# Power.net
KiCad netlist of a schematic drawn in Altium Designer
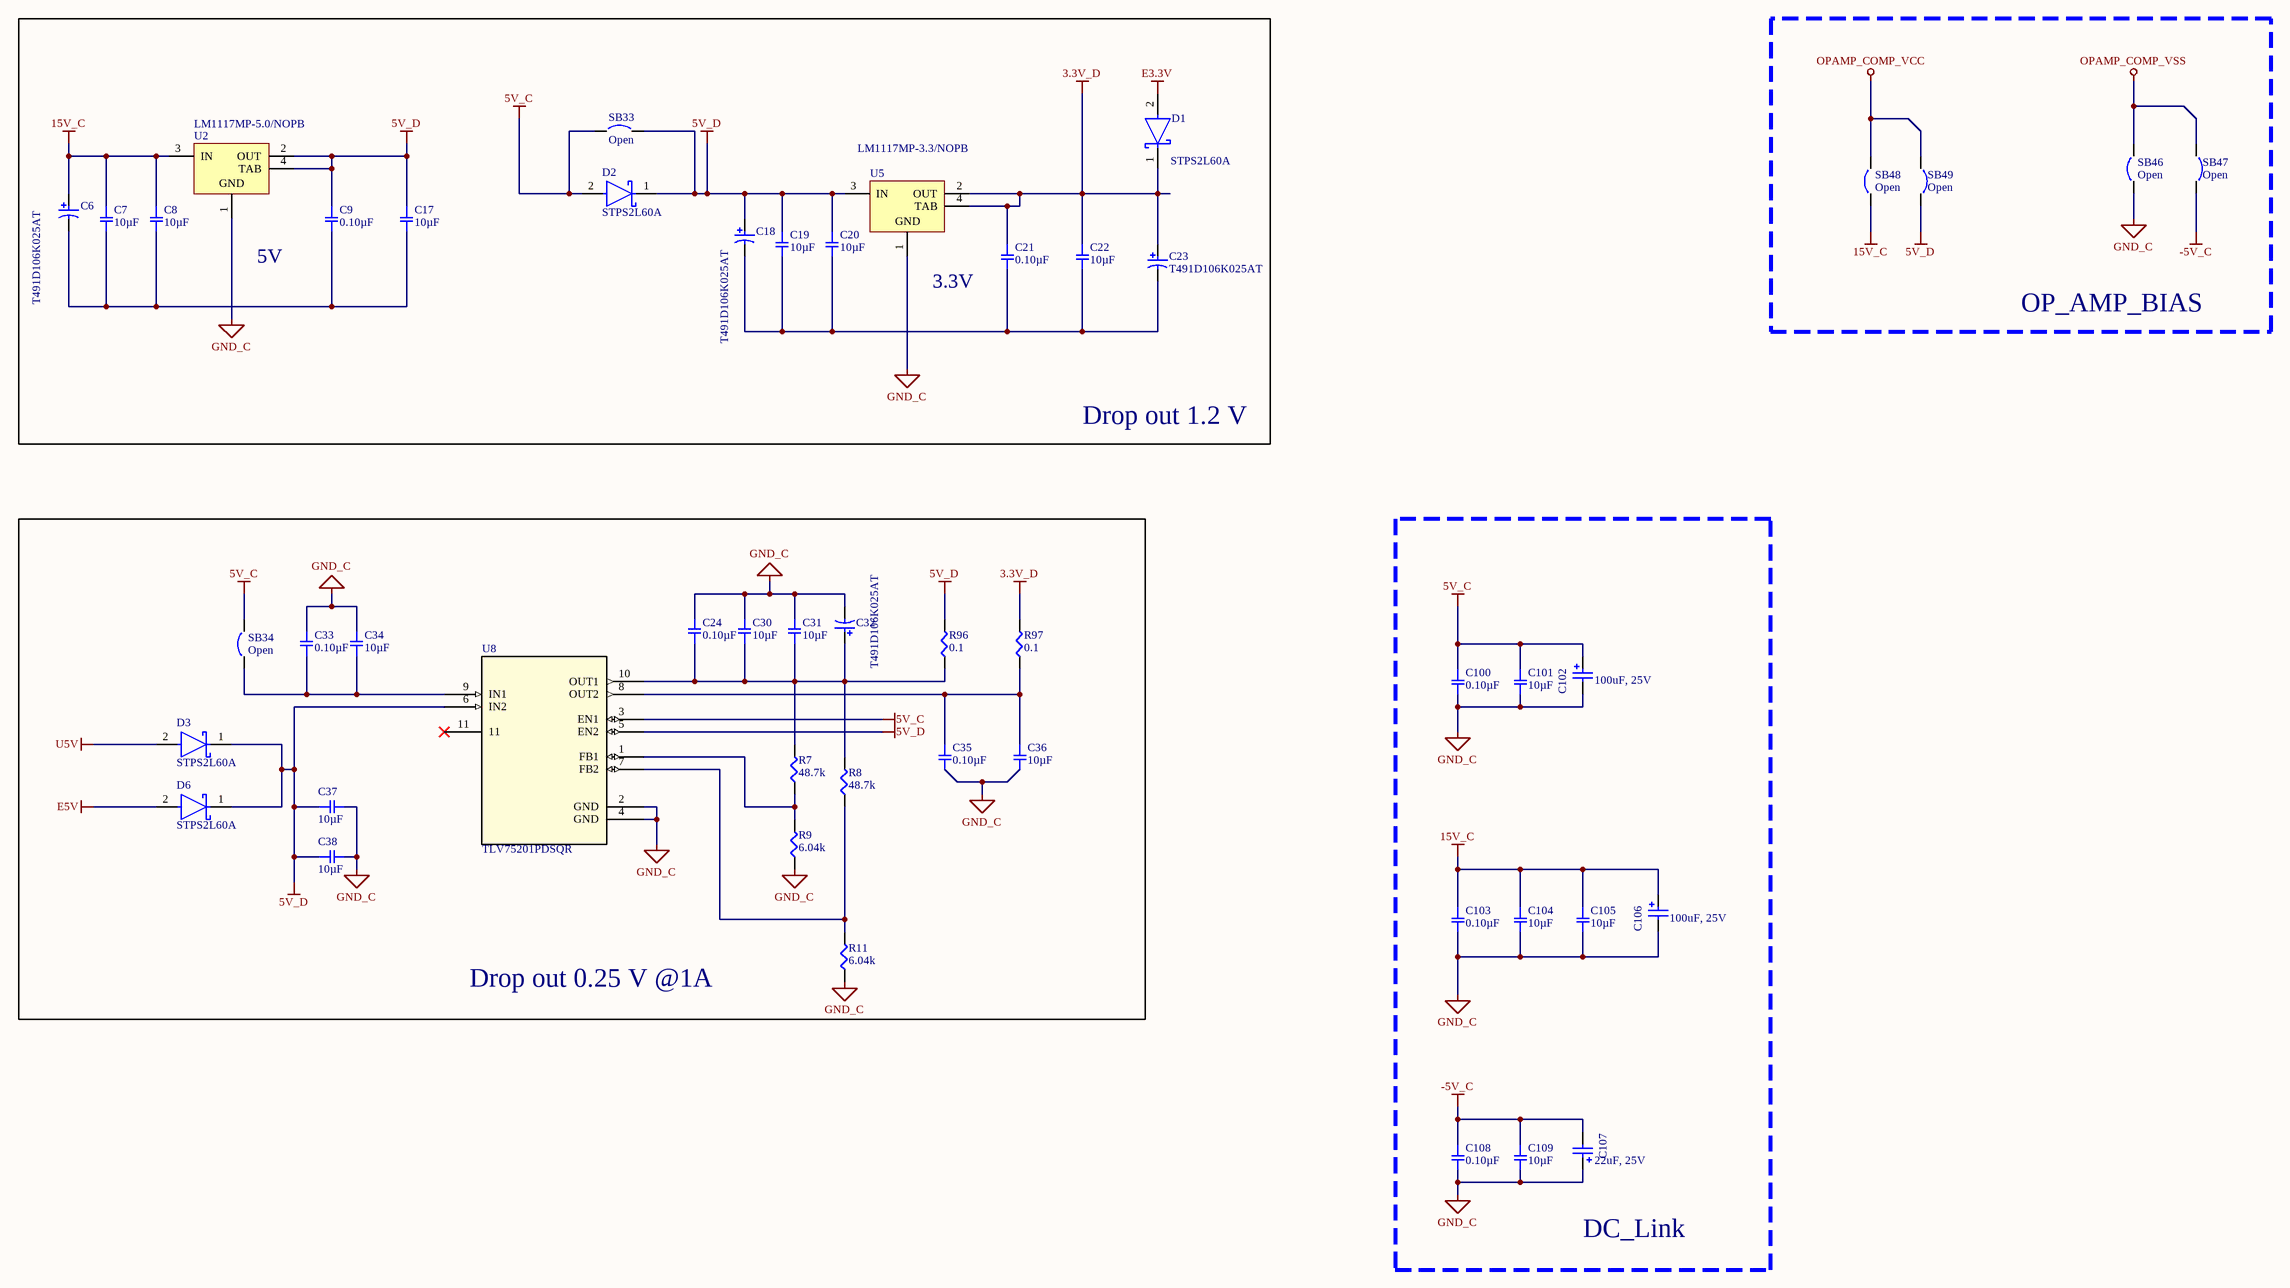
[diagram p0: Power.SchDoc]

(export (version "E")
  (design (tool "Eeschema 10.0.6"))
  (components
    (comp (ref "C6")
      (value "T491D106K025AT")
      (footprint "KEMT-T491-D_L")
      (description "Tantalum Capacitor, 10 uF, +/- 10%, 25 V, -55 to 125 degC, 2-Pin SMD, RoHS, Tape and Reel")
      (fields (field (name "MANUFACTURER") "Kemet") (field (name "VOLTAGE") "25VDC"))
      (libsource (lib "Altium Content Vault") (part "CAP-P-2"))
    )
    (comp (ref "C7")
      (value "10µF")
      (footprint "SMD-0805C")
      (description "CAP CER 10UF 10V X7R 0805")
      (fields
        (field (name "DIGI-KEY PART NUMBER") "490-10674-1-ND")
        (field (name "PART NUMBER") "GCM21BR71A106KE22L")
      )
      (libsource (lib "capacitor_murata_0805") (part "GCM21BR71A106KE22L"))
    )
    (comp (ref "C8")
      (value "10µF")
      (footprint "SMD-0805C")
      (description "CAP CER 10UF 10V X7R 0805")
      (fields
        (field (name "DIGI-KEY PART NUMBER") "490-10674-1-ND")
        (field (name "PART NUMBER") "GCM21BR71A106KE22L")
      )
      (libsource (lib "capacitor_murata_0805") (part "GCM21BR71A106KE22L"))
    )
    (comp (ref "C9")
      (value "0.10µF")
      (footprint "SMD-0805C")
      (description "CAP CER 0.1UF 100V X7R 0805")
      (fields
        (field (name "DIGI-KEY PART NUMBER") "490-5825-1-ND")
        (field (name "PART NUMBER") "GCJ21BR72A104KA01L")
      )
      (libsource (lib "capacitor_murata_0805") (part "GCJ21BR72A104KA01L"))
    )
    (comp (ref "C17")
      (value "10µF")
      (footprint "SMD-0805C")
      (description "CAP CER 10UF 10V X7R 0805")
      (fields
        (field (name "DIGI-KEY PART NUMBER") "490-10674-1-ND")
        (field (name "PART NUMBER") "GCM21BR71A106KE22L")
      )
      (libsource (lib "capacitor_murata_0805") (part "GCM21BR71A106KE22L"))
    )
    (comp (ref "C18")
      (value "T491D106K025AT")
      (footprint "KEMT-T491-D_L")
      (description "Tantalum Capacitor, 10 uF, +/- 10%, 25 V, -55 to 125 degC, 2-Pin SMD, RoHS, Tape and Reel")
      (fields (field (name "MANUFACTURER") "Kemet") (field (name "VOLTAGE") "25VDC"))
      (libsource (lib "Altium Content Vault") (part "CAP-P-2"))
    )
    (comp (ref "C19")
      (value "10µF")
      (footprint "SMD-0805C")
      (description "CAP CER 10UF 10V X7R 0805")
      (fields
        (field (name "DIGI-KEY PART NUMBER") "490-10674-1-ND")
        (field (name "PART NUMBER") "GCM21BR71A106KE22L")
      )
      (libsource (lib "capacitor_murata_0805") (part "GCM21BR71A106KE22L"))
    )
    (comp (ref "C20")
      (value "10µF")
      (footprint "SMD-0805C")
      (description "CAP CER 10UF 10V X7R 0805")
      (fields
        (field (name "DIGI-KEY PART NUMBER") "490-10674-1-ND")
        (field (name "PART NUMBER") "GCM21BR71A106KE22L")
      )
      (libsource (lib "capacitor_murata_0805") (part "GCM21BR71A106KE22L"))
    )
    (comp (ref "C21")
      (value "0.10µF")
      (footprint "SMD-0805C")
      (description "CAP CER 0.1UF 100V X7R 0805")
      (fields
        (field (name "DIGI-KEY PART NUMBER") "490-5825-1-ND")
        (field (name "PART NUMBER") "GCJ21BR72A104KA01L")
      )
      (libsource (lib "capacitor_murata_0805") (part "GCJ21BR72A104KA01L"))
    )
    (comp (ref "C22")
      (value "10µF")
      (footprint "SMD-0805C")
      (description "CAP CER 10UF 10V X7R 0805")
      (fields
        (field (name "DIGI-KEY PART NUMBER") "490-10674-1-ND")
        (field (name "PART NUMBER") "GCM21BR71A106KE22L")
      )
      (libsource (lib "capacitor_murata_0805") (part "GCM21BR71A106KE22L"))
    )
    (comp (ref "C23")
      (value "T491D106K025AT")
      (footprint "KEMT-T491-D_L")
      (description "Tantalum Capacitor, 10 uF, +/- 10%, 25 V, -55 to 125 degC, 2-Pin SMD, RoHS, Tape and Reel")
      (fields (field (name "MANUFACTURER") "Kemet") (field (name "VOLTAGE") "25VDC"))
      (libsource (lib "Altium Content Vault") (part "CAP-P-2"))
    )
    (comp (ref "C24")
      (value "0.10µF")
      (footprint "SMD-0805C")
      (description "CAP CER 0.1UF 100V X7R 0805")
      (fields
        (field (name "DIGI-KEY PART NUMBER") "490-5825-1-ND")
        (field (name "PART NUMBER") "GCJ21BR72A104KA01L")
      )
      (libsource (lib "capacitor_murata_0805") (part "GCJ21BR72A104KA01L"))
    )
    (comp (ref "C30")
      (value "10µF")
      (footprint "SMD-0805C")
      (description "CAP CER 10UF 10V X7R 0805")
      (fields
        (field (name "DIGI-KEY PART NUMBER") "490-10674-1-ND")
        (field (name "PART NUMBER") "GCM21BR71A106KE22L")
      )
      (libsource (lib "capacitor_murata_0805") (part "GCM21BR71A106KE22L"))
    )
    (comp (ref "C31")
      (value "10µF")
      (footprint "SMD-0805C")
      (description "CAP CER 10UF 10V X7R 0805")
      (fields
        (field (name "DIGI-KEY PART NUMBER") "490-10674-1-ND")
        (field (name "PART NUMBER") "GCM21BR71A106KE22L")
      )
      (libsource (lib "capacitor_murata_0805") (part "GCM21BR71A106KE22L"))
    )
    (comp (ref "C32")
      (value "T491D106K025AT")
      (footprint "KEMT-T491-D_L")
      (description "Tantalum Capacitor, 10 uF, +/- 10%, 25 V, -55 to 125 degC, 2-Pin SMD, RoHS, Tape and Reel")
      (fields (field (name "MANUFACTURER") "Kemet") (field (name "VOLTAGE") "25VDC"))
      (libsource (lib "Altium Content Vault") (part "CAP-P-2"))
    )
    (comp (ref "C33")
      (value "0.10µF")
      (footprint "SMD-0805C")
      (description "CAP CER 0.1UF 100V X7R 0805")
      (fields
        (field (name "DIGI-KEY PART NUMBER") "490-5825-1-ND")
        (field (name "PART NUMBER") "GCJ21BR72A104KA01L")
      )
      (libsource (lib "capacitor_murata_0805") (part "GCJ21BR72A104KA01L"))
    )
    (comp (ref "C34")
      (value "10µF")
      (footprint "SMD-0805C")
      (description "CAP CER 10UF 10V X7R 0805")
      (fields
        (field (name "DIGI-KEY PART NUMBER") "490-10674-1-ND")
        (field (name "PART NUMBER") "GCM21BR71A106KE22L")
      )
      (libsource (lib "capacitor_murata_0805") (part "GCM21BR71A106KE22L"))
    )
    (comp (ref "C35")
      (value "0.10µF")
      (footprint "SMD-0805C")
      (description "CAP CER 0.1UF 100V X7R 0805")
      (fields
        (field (name "DIGI-KEY PART NUMBER") "490-5825-1-ND")
        (field (name "PART NUMBER") "GCJ21BR72A104KA01L")
      )
      (libsource (lib "capacitor_murata_0805") (part "GCJ21BR72A104KA01L"))
    )
    (comp (ref "C36")
      (value "10µF")
      (footprint "SMD-0805C")
      (description "CAP CER 10UF 10V X7R 0805")
      (fields
        (field (name "DIGI-KEY PART NUMBER") "490-10674-1-ND")
        (field (name "PART NUMBER") "GCM21BR71A106KE22L")
      )
      (libsource (lib "capacitor_murata_0805") (part "GCM21BR71A106KE22L"))
    )
    (comp (ref "C37")
      (value "10µF")
      (footprint "SMD-0805C")
      (description "CAP CER 10UF 10V X7R 0805")
      (fields
        (field (name "DIGI-KEY PART NUMBER") "490-10674-1-ND")
        (field (name "PART NUMBER") "GCM21BR71A106KE22L")
      )
      (libsource (lib "capacitor_murata_0805") (part "GCM21BR71A106KE22L"))
    )
    (comp (ref "C38")
      (value "10µF")
      (footprint "SMD-0805C")
      (description "CAP CER 10UF 10V X7R 0805")
      (fields
        (field (name "DIGI-KEY PART NUMBER") "490-10674-1-ND")
        (field (name "PART NUMBER") "GCM21BR71A106KE22L")
      )
      (libsource (lib "capacitor_murata_0805") (part "GCM21BR71A106KE22L"))
    )
    (comp (ref "C100")
      (value "0.10µF")
      (footprint "SMD-0805C")
      (description "CAP CER 0.1UF 100V X7R 0805")
      (fields
        (field (name "DIGI-KEY PART NUMBER") "490-5825-1-ND")
        (field (name "PART NUMBER") "GCJ21BR72A104KA01L")
      )
      (libsource (lib "capacitor_murata_0805") (part "GCJ21BR72A104KA01L"))
    )
    (comp (ref "C101")
      (value "10µF")
      (footprint "SMD-0805C")
      (description "CAP CER 10UF 10V X7R 0805")
      (fields
        (field (name "DIGI-KEY PART NUMBER") "490-10674-1-ND")
        (field (name "PART NUMBER") "GCM21BR71A106KE22L")
      )
      (libsource (lib "capacitor_murata_0805") (part "GCM21BR71A106KE22L"))
    )
    (comp (ref "C102")
      (value "100uF, 25V")
      (footprint "WCAP-ASLU_6.3x7.7")
      (description "WCAP-ASLU Aluminium Electrolytic Capacitors, D6.3mm x L7.7mm, 100uF, +/-20%, 25VDC")
      (fields (field (name "PART NUMBER") "865090445008") (field (name "PUBLISHER") "Wurth Elektronik"))
      (libsource (lib "Altium_WCAP-ASLU_SMD") (part "865090445008"))
    )
    (comp (ref "C103")
      (value "0.10µF")
      (footprint "SMD-0805C")
      (description "CAP CER 0.1UF 100V X7R 0805")
      (fields
        (field (name "DIGI-KEY PART NUMBER") "490-5825-1-ND")
        (field (name "PART NUMBER") "GCJ21BR72A104KA01L")
      )
      (libsource (lib "capacitor_murata_0805") (part "GCJ21BR72A104KA01L"))
    )
    (comp (ref "C104")
      (value "10µF")
      (footprint "SMD-0805C")
      (description "CAP CER 10UF 10V X7R 0805")
      (fields
        (field (name "DIGI-KEY PART NUMBER") "490-10674-1-ND")
        (field (name "PART NUMBER") "GCM21BR71A106KE22L")
      )
      (libsource (lib "capacitor_murata_0805") (part "GCM21BR71A106KE22L"))
    )
    (comp (ref "C105")
      (value "10µF")
      (footprint "SMD-0805C")
      (description "CAP CER 10UF 10V X7R 0805")
      (fields
        (field (name "DIGI-KEY PART NUMBER") "490-10674-1-ND")
        (field (name "PART NUMBER") "GCM21BR71A106KE22L")
      )
      (libsource (lib "capacitor_murata_0805") (part "GCM21BR71A106KE22L"))
    )
    (comp (ref "C106")
      (value "100uF, 25V")
      (footprint "WCAP-ASLU_6.3x7.7")
      (description "WCAP-ASLU Aluminium Electrolytic Capacitors, D6.3mm x L7.7mm, 100uF, +/-20%, 25VDC")
      (fields (field (name "PART NUMBER") "865090445008") (field (name "PUBLISHER") "Wurth Elektronik"))
      (libsource (lib "Altium_WCAP-ASLU_SMD") (part "865090445008"))
    )
    (comp (ref "C107")
      (value "22uF, 25V")
      (footprint "WCAP-ASLU_5x5.5")
      (description "WCAP-ASLU Aluminium Electrolytic Capacitors, D5mm x L5.5mm, 22uF, +/-20%, 25VDC")
      (fields (field (name "PART NUMBER") "865090442004") (field (name "PUBLISHER") "Wurth Elektronik"))
      (libsource (lib "Altium_WCAP-ASLU_SMD") (part "865090442004"))
    )
    (comp (ref "C108")
      (value "0.10µF")
      (footprint "SMD-0805C")
      (description "CAP CER 0.1UF 100V X7R 0805")
      (fields
        (field (name "DIGI-KEY PART NUMBER") "490-5825-1-ND")
        (field (name "PART NUMBER") "GCJ21BR72A104KA01L")
      )
      (libsource (lib "capacitor_murata_0805") (part "GCJ21BR72A104KA01L"))
    )
    (comp (ref "C109")
      (value "10µF")
      (footprint "SMD-0805C")
      (description "CAP CER 10UF 10V X7R 0805")
      (fields
        (field (name "DIGI-KEY PART NUMBER") "490-10674-1-ND")
        (field (name "PART NUMBER") "GCM21BR71A106KE22L")
      )
      (libsource (lib "capacitor_murata_0805") (part "GCM21BR71A106KE22L"))
    )
    (comp (ref "D1")
      (value "STPS2L60A")
      (footprint "FP-SMA-MFG")
      (description "DIODE SCHOTTKY 60V 2A SMA")
      (fields
        (field (name "OCTOPART") "https://octopart.com/stps2l60a-stmicroelectronics-324283")
        (field (name "MANUFACTURER") "STMicroelectronics")
      )
      (libsource (lib "Altium Content Vault") (part "fefb30dabb5d097ae2f038500735429"))
    )
    (comp (ref "D2")
      (value "STPS2L60A")
      (footprint "FP-SMA-MFG")
      (description "DIODE SCHOTTKY 60V 2A SMA")
      (fields
        (field (name "OCTOPART") "https://octopart.com/stps2l60a-stmicroelectronics-324283")
        (field (name "MANUFACTURER") "STMicroelectronics")
      )
      (libsource (lib "Altium Content Vault") (part "fefb30dabb5d097ae2f038500735429"))
    )
    (comp (ref "D3")
      (value "STPS2L60A")
      (footprint "FP-SMA-MFG")
      (description "DIODE SCHOTTKY 60V 2A SMA")
      (fields
        (field (name "OCTOPART") "https://octopart.com/stps2l60a-stmicroelectronics-324283")
        (field (name "MANUFACTURER") "STMicroelectronics")
      )
      (libsource (lib "Altium Content Vault") (part "fefb30dabb5d097ae2f038500735429"))
    )
    (comp (ref "D6")
      (value "STPS2L60A")
      (footprint "FP-SMA-MFG")
      (description "DIODE SCHOTTKY 60V 2A SMA")
      (fields
        (field (name "OCTOPART") "https://octopart.com/stps2l60a-stmicroelectronics-324283")
        (field (name "MANUFACTURER") "STMicroelectronics")
      )
      (libsource (lib "Altium Content Vault") (part "fefb30dabb5d097ae2f038500735429"))
    )
    (comp (ref "R7")
      (value "48.7k")
      (footprint "SMD-0603-RES")
      (description "RES SMD 48.7K OHM 1% 1/10W 0603")
      (fields
        (field (name "PART NUMBER") "ERJ-3EKF4872V")
        (field (name "DIGI-KEY PART NUMBER") "P48.7KHCT-ND")
      )
      (libsource (lib "Panasonic_ERJ_0603") (part "ERJ-3EKF4872V"))
    )
    (comp (ref "R8")
      (value "48.7k")
      (footprint "SMD-0603-RES")
      (description "RES SMD 48.7K OHM 1% 1/10W 0603")
      (fields
        (field (name "PART NUMBER") "ERJ-3EKF4872V")
        (field (name "DIGI-KEY PART NUMBER") "P48.7KHCT-ND")
      )
      (libsource (lib "Panasonic_ERJ_0603") (part "ERJ-3EKF4872V"))
    )
    (comp (ref "R9")
      (value "6.04k")
      (footprint "SMD-0603-RES")
      (description "RES SMD 6.04K OHM 1% 1/10W 0603")
      (fields
        (field (name "PART NUMBER") "ERJ-3EKF6041V")
        (field (name "DIGI-KEY PART NUMBER") "P6.04KHCT-ND")
      )
      (libsource (lib "Panasonic_ERJ_0603") (part "ERJ-3EKF6041V"))
    )
    (comp (ref "R11")
      (value "6.04k")
      (footprint "SMD-0603-RES")
      (description "RES SMD 6.04K OHM 1% 1/10W 0603")
      (fields
        (field (name "PART NUMBER") "ERJ-3EKF6041V")
        (field (name "DIGI-KEY PART NUMBER") "P6.04KHCT-ND")
      )
      (libsource (lib "Panasonic_ERJ_0603") (part "ERJ-3EKF6041V"))
    )
    (comp (ref "R96")
      (value "0.1")
      (footprint "SMD-1206-RES")
      (description "RES SMD 0.1 OHM 1% 1/2W 1206")
      (fields (field (name "PART NUMBER") "ERJ-8BSFR10V") (field (name "DIGI-KEY PART NUMBER") "P17678CT-ND"))
      (libsource (lib "Panasonic_ERJ_1206") (part "ERJ-8BSFR10V"))
    )
    (comp (ref "R97")
      (value "0.1")
      (footprint "SMD-1206-RES")
      (description "RES SMD 0.1 OHM 1% 1/2W 1206")
      (fields (field (name "PART NUMBER") "ERJ-8BSFR10V") (field (name "DIGI-KEY PART NUMBER") "P17678CT-ND"))
      (libsource (lib "Panasonic_ERJ_1206") (part "ERJ-8BSFR10V"))
    )
    (comp (ref "SB33")
      (value "Open")
      (footprint "SB_0603")
      (description "Circuit Breaker")
      (fields (field (name "PUBLISHER") "Altium Limited"))
      (libsource (lib "Edge_Card_Ucc28951") (part "Solder Bridge"))
    )
    (comp (ref "SB34")
      (value "Open")
      (footprint "SB_0603")
      (description "Circuit Breaker")
      (fields (field (name "PUBLISHER") "Altium Limited"))
      (libsource (lib "Edge_Card_Ucc28951") (part "Solder Bridge"))
    )
    (comp (ref "SB46")
      (value "Open")
      (footprint "Solder Bridge - HP")
      (description "Circuit Breaker")
      (fields (field (name "PUBLISHER") "Altium Limited"))
      (libsource (lib "Edge_Card_Ucc28951") (part "Solder Bridge"))
    )
    (comp (ref "SB47")
      (value "Open")
      (footprint "Solder Bridge - HP")
      (description "Circuit Breaker")
      (fields (field (name "PUBLISHER") "Altium Limited"))
      (libsource (lib "") (part "Solder Bridge_1"))
    )
    (comp (ref "SB48")
      (value "Open")
      (footprint "Solder Bridge - HP")
      (description "Circuit Breaker")
      (fields (field (name "PUBLISHER") "Altium Limited"))
      (libsource (lib "Edge_Card_Ucc28951") (part "Solder Bridge"))
    )
    (comp (ref "SB49")
      (value "Open")
      (footprint "Solder Bridge - HP")
      (description "Circuit Breaker")
      (fields (field (name "PUBLISHER") "Altium Limited"))
      (libsource (lib "") (part "Solder Bridge_1"))
    )
    (comp (ref "U2")
      (value "LM1117MP-5.0/NOPB")
      (footprint "DCY0004A_N")
      (description "800mA Low-Dropout Linear Regulator, 4-pin SOT-223, Pb-Free")
      (fields (field (name "MANUFACTURER") "Texas Instruments"))
      (libsource (lib "Altium Content Vault") (part "PM-REG-LM1086-SOT4"))
    )
    (comp (ref "U5")
      (value "LM1117MP-3.3/NOPB")
      (footprint "DCY0004A_L")
      (description "800mA Low-Dropout Linear Regulator, 4-pin SOT-223, Pb-Free")
      (fields (field (name "MANUFACTURER") "Texas Instruments"))
      (libsource (lib "Altium Content Vault") (part "PM-REG-LM1086-SOT4"))
    )
    (comp (ref "U8")
      (value "TLV75201PDSQR")
      (footprint "SON40P200X80_HS-11N")
      (description "No Description Available")
      (fields (field (name "COPYRIGHT") "Copyright (C) 2018 Accelerated Designs. All rights reserved"))
      (libsource (lib "Edge_Card_Ucc28951") (part "TLV75201PDSQR"))
    )
  )
  (nets
    (net (code "1") (name "-5V_C") (class "Default")
      (node (ref "C107") (pin "1") (pinfunction "N_1") (pintype "passive"))
      (node (ref "C108") (pin "1") (pinfunction "1_1") (pintype "passive"))
      (node (ref "C109") (pin "1") (pinfunction "1_1") (pintype "passive"))
      (node (ref "SB47") (pin "1") (pinfunction "1_1") (pintype "passive"))
    )
    (net (code "2") (name "3.3V_D") (class "Default")
      (node (ref "C21") (pin "1") (pinfunction "1_1") (pintype "passive"))
      (node (ref "C22") (pin "1") (pinfunction "1_1") (pintype "passive"))
      (node (ref "C23") (pin "1") (pinfunction "1_1") (pintype "passive"))
      (node (ref "D1") (pin "1") (pinfunction "K_1") (pintype "passive"))
      (node (ref "R97") (pin "2") (pinfunction "2_2") (pintype "passive"))
      (node (ref "U5") (pin "2") (pinfunction "OUT_2") (pintype "power_in"))
      (node (ref "U5") (pin "4") (pinfunction "TAB_4") (pintype "power_in"))
    )
    (net (code "3") (name "5V_C") (class "Default")
      (node (ref "C100") (pin "1") (pinfunction "1_1") (pintype "passive"))
      (node (ref "C101") (pin "1") (pinfunction "1_1") (pintype "passive"))
      (node (ref "C102") (pin "2") (pinfunction "P_2") (pintype "passive"))
      (node (ref "D2") (pin "2") (pinfunction "A_2") (pintype "passive"))
      (node (ref "SB33") (pin "1") (pinfunction "1_1") (pintype "passive"))
      (node (ref "SB34") (pin "2") (pinfunction "2_2") (pintype "passive"))
      (node (ref "U8") (pin "3") (pinfunction "EN1_3") (pintype "bidirectional"))
    )
    (net (code "4") (name "5V_D") (class "Default")
      (node (ref "C17") (pin "1") (pinfunction "1_1") (pintype "passive"))
      (node (ref "C18") (pin "1") (pinfunction "1_1") (pintype "passive"))
      (node (ref "C19") (pin "1") (pinfunction "1_1") (pintype "passive"))
      (node (ref "C20") (pin "1") (pinfunction "1_1") (pintype "passive"))
      (node (ref "C37") (pin "1") (pinfunction "1_1") (pintype "passive"))
      (node (ref "C38") (pin "1") (pinfunction "1_1") (pintype "passive"))
      (node (ref "C9") (pin "1") (pinfunction "1_1") (pintype "passive"))
      (node (ref "D2") (pin "1") (pinfunction "K_1") (pintype "passive"))
      (node (ref "D3") (pin "1") (pinfunction "K_1") (pintype "passive"))
      (node (ref "D6") (pin "1") (pinfunction "K_1") (pintype "passive"))
      (node (ref "R96") (pin "2") (pinfunction "2_2") (pintype "passive"))
      (node (ref "SB33") (pin "2") (pinfunction "2_2") (pintype "passive"))
      (node (ref "SB49") (pin "1") (pinfunction "1_1") (pintype "passive"))
      (node (ref "U2") (pin "2") (pinfunction "OUT_2") (pintype "power_in"))
      (node (ref "U2") (pin "4") (pinfunction "TAB_4") (pintype "power_in"))
      (node (ref "U5") (pin "3") (pinfunction "IN_3") (pintype "power_in"))
      (node (ref "U8") (pin "5") (pinfunction "EN2_5") (pintype "bidirectional"))
      (node (ref "U8") (pin "6") (pinfunction "IN2_6") (pintype "input"))
    )
    (net (code "5") (name "15V_C") (class "Default")
      (node (ref "C103") (pin "1") (pinfunction "1_1") (pintype "passive"))
      (node (ref "C104") (pin "1") (pinfunction "1_1") (pintype "passive"))
      (node (ref "C105") (pin "1") (pinfunction "1_1") (pintype "passive"))
      (node (ref "C106") (pin "2") (pinfunction "P_2") (pintype "passive"))
      (node (ref "C6") (pin "1") (pinfunction "1_1") (pintype "passive"))
      (node (ref "C7") (pin "1") (pinfunction "1_1") (pintype "passive"))
      (node (ref "C8") (pin "1") (pinfunction "1_1") (pintype "passive"))
      (node (ref "SB48") (pin "1") (pinfunction "1_1") (pintype "passive"))
      (node (ref "U2") (pin "3") (pinfunction "IN_3") (pintype "power_in"))
    )
    (net (code "6") (name "E3.3V") (class "Default")
      (node (ref "D1") (pin "2") (pinfunction "A_2") (pintype "passive"))
    )
    (net (code "7") (name "E5V") (class "Default")
      (node (ref "D6") (pin "2") (pinfunction "A_2") (pintype "passive"))
    )
    (net (code "8") (name "GND_C") (class "Default")
      (node (ref "C100") (pin "2") (pinfunction "2_2") (pintype "passive"))
      (node (ref "C101") (pin "2") (pinfunction "2_2") (pintype "passive"))
      (node (ref "C102") (pin "1") (pinfunction "N_1") (pintype "passive"))
      (node (ref "C103") (pin "2") (pinfunction "2_2") (pintype "passive"))
      (node (ref "C104") (pin "2") (pinfunction "2_2") (pintype "passive"))
      (node (ref "C105") (pin "2") (pinfunction "2_2") (pintype "passive"))
      (node (ref "C106") (pin "1") (pinfunction "N_1") (pintype "passive"))
      (node (ref "C107") (pin "2") (pinfunction "P_2") (pintype "passive"))
      (node (ref "C108") (pin "2") (pinfunction "2_2") (pintype "passive"))
      (node (ref "C109") (pin "2") (pinfunction "2_2") (pintype "passive"))
      (node (ref "C24") (pin "2") (pinfunction "2_2") (pintype "passive"))
      (node (ref "C30") (pin "2") (pinfunction "2_2") (pintype "passive"))
      (node (ref "C31") (pin "2") (pinfunction "2_2") (pintype "passive"))
      (node (ref "C32") (pin "2") (pinfunction "2_2") (pintype "passive"))
      (node (ref "C33") (pin "2") (pinfunction "2_2") (pintype "passive"))
      (node (ref "C34") (pin "2") (pinfunction "2_2") (pintype "passive"))
      (node (ref "C35") (pin "2") (pinfunction "2_2") (pintype "passive"))
      (node (ref "C36") (pin "2") (pinfunction "2_2") (pintype "passive"))
      (node (ref "C37") (pin "2") (pinfunction "2_2") (pintype "passive"))
      (node (ref "C38") (pin "2") (pinfunction "2_2") (pintype "passive"))
      (node (ref "R11") (pin "1") (pinfunction "1_1") (pintype "passive"))
      (node (ref "R9") (pin "1") (pinfunction "1_1") (pintype "passive"))
      (node (ref "SB46") (pin "1") (pinfunction "1_1") (pintype "passive"))
      (node (ref "U2") (pin "1") (pinfunction "GND_1") (pintype "power_in"))
      (node (ref "U5") (pin "1") (pinfunction "GND_1") (pintype "power_in"))
      (node (ref "U8") (pin "2") (pinfunction "GND_2") (pintype "passive"))
      (node (ref "U8") (pin "4") (pinfunction "GND_4") (pintype "passive"))
    )
    (net (code "9") (name "Net-(C17-Pad2)") (class "Default")
      (node (ref "C17") (pin "2") (pinfunction "2_2") (pintype "passive"))
      (node (ref "C6") (pin "2") (pinfunction "2_2") (pintype "passive"))
      (node (ref "C7") (pin "2") (pinfunction "2_2") (pintype "passive"))
      (node (ref "C8") (pin "2") (pinfunction "2_2") (pintype "passive"))
      (node (ref "C9") (pin "2") (pinfunction "2_2") (pintype "passive"))
    )
    (net (code "10") (name "Net-(C18-Pad2)") (class "Default")
      (node (ref "C18") (pin "2") (pinfunction "2_2") (pintype "passive"))
      (node (ref "C19") (pin "2") (pinfunction "2_2") (pintype "passive"))
      (node (ref "C20") (pin "2") (pinfunction "2_2") (pintype "passive"))
      (node (ref "C21") (pin "2") (pinfunction "2_2") (pintype "passive"))
      (node (ref "C22") (pin "2") (pinfunction "2_2") (pintype "passive"))
      (node (ref "C23") (pin "2") (pinfunction "2_2") (pintype "passive"))
    )
    (net (code "11") (name "Net-(U8-FB1)") (class "Default")
      (node (ref "R7") (pin "1") (pinfunction "1_1") (pintype "passive"))
      (node (ref "R9") (pin "2") (pinfunction "2_2") (pintype "passive"))
      (node (ref "U8") (pin "1") (pinfunction "FB1_1") (pintype "bidirectional"))
    )
    (net (code "12") (name "Net-(U8-FB2)") (class "Default")
      (node (ref "R11") (pin "2") (pinfunction "2_2") (pintype "passive"))
      (node (ref "R8") (pin "1") (pinfunction "1_1") (pintype "passive"))
      (node (ref "U8") (pin "7") (pinfunction "FB2_7") (pintype "bidirectional"))
    )
    (net (code "13") (name "Net-(U8-IN1)") (class "Default")
      (node (ref "C33") (pin "1") (pinfunction "1_1") (pintype "passive"))
      (node (ref "C34") (pin "1") (pinfunction "1_1") (pintype "passive"))
      (node (ref "SB34") (pin "1") (pinfunction "1_1") (pintype "passive"))
      (node (ref "U8") (pin "9") (pinfunction "IN1_9") (pintype "input"))
    )
    (net (code "14") (name "Net-(U8-OUT1)") (class "Default")
      (node (ref "C24") (pin "1") (pinfunction "1_1") (pintype "passive"))
      (node (ref "C30") (pin "1") (pinfunction "1_1") (pintype "passive"))
      (node (ref "C31") (pin "1") (pinfunction "1_1") (pintype "passive"))
      (node (ref "C32") (pin "1") (pinfunction "1_1") (pintype "passive"))
      (node (ref "R7") (pin "2") (pinfunction "2_2") (pintype "passive"))
      (node (ref "R8") (pin "2") (pinfunction "2_2") (pintype "passive"))
      (node (ref "R96") (pin "1") (pinfunction "1_1") (pintype "passive"))
      (node (ref "U8") (pin "10") (pinfunction "OUT1_10") (pintype "output"))
    )
    (net (code "15") (name "Net-(U8-OUT2)") (class "Default")
      (node (ref "C35") (pin "1") (pinfunction "1_1") (pintype "passive"))
      (node (ref "C36") (pin "1") (pinfunction "1_1") (pintype "passive"))
      (node (ref "R97") (pin "1") (pinfunction "1_1") (pintype "passive"))
      (node (ref "U8") (pin "8") (pinfunction "OUT2_8") (pintype "output"))
    )
    (net (code "16") (name "OPAMP_COMP_VCC") (class "Default")
      (node (ref "SB48") (pin "2") (pinfunction "2_2") (pintype "passive"))
      (node (ref "SB49") (pin "2") (pinfunction "2_2") (pintype "passive"))
    )
    (net (code "17") (name "OPAMP_COMP_VSS") (class "Default")
      (node (ref "SB46") (pin "2") (pinfunction "2_2") (pintype "passive"))
      (node (ref "SB47") (pin "2") (pinfunction "2_2") (pintype "passive"))
    )
    (net (code "18") (name "U5V") (class "Default")
      (node (ref "D3") (pin "2") (pinfunction "A_2") (pintype "passive"))
    )
    (net (code "19") (name "unconnected-(U8-Pad11)") (class "Default")
      (node (ref "U8") (pin "11") (pinfunction "11_11") (pintype "passive+no_connect"))
    )
  )
)
